# DDC118_eval2_rev1D.net
KiCad netlist of a schematic drawn in EAGLE
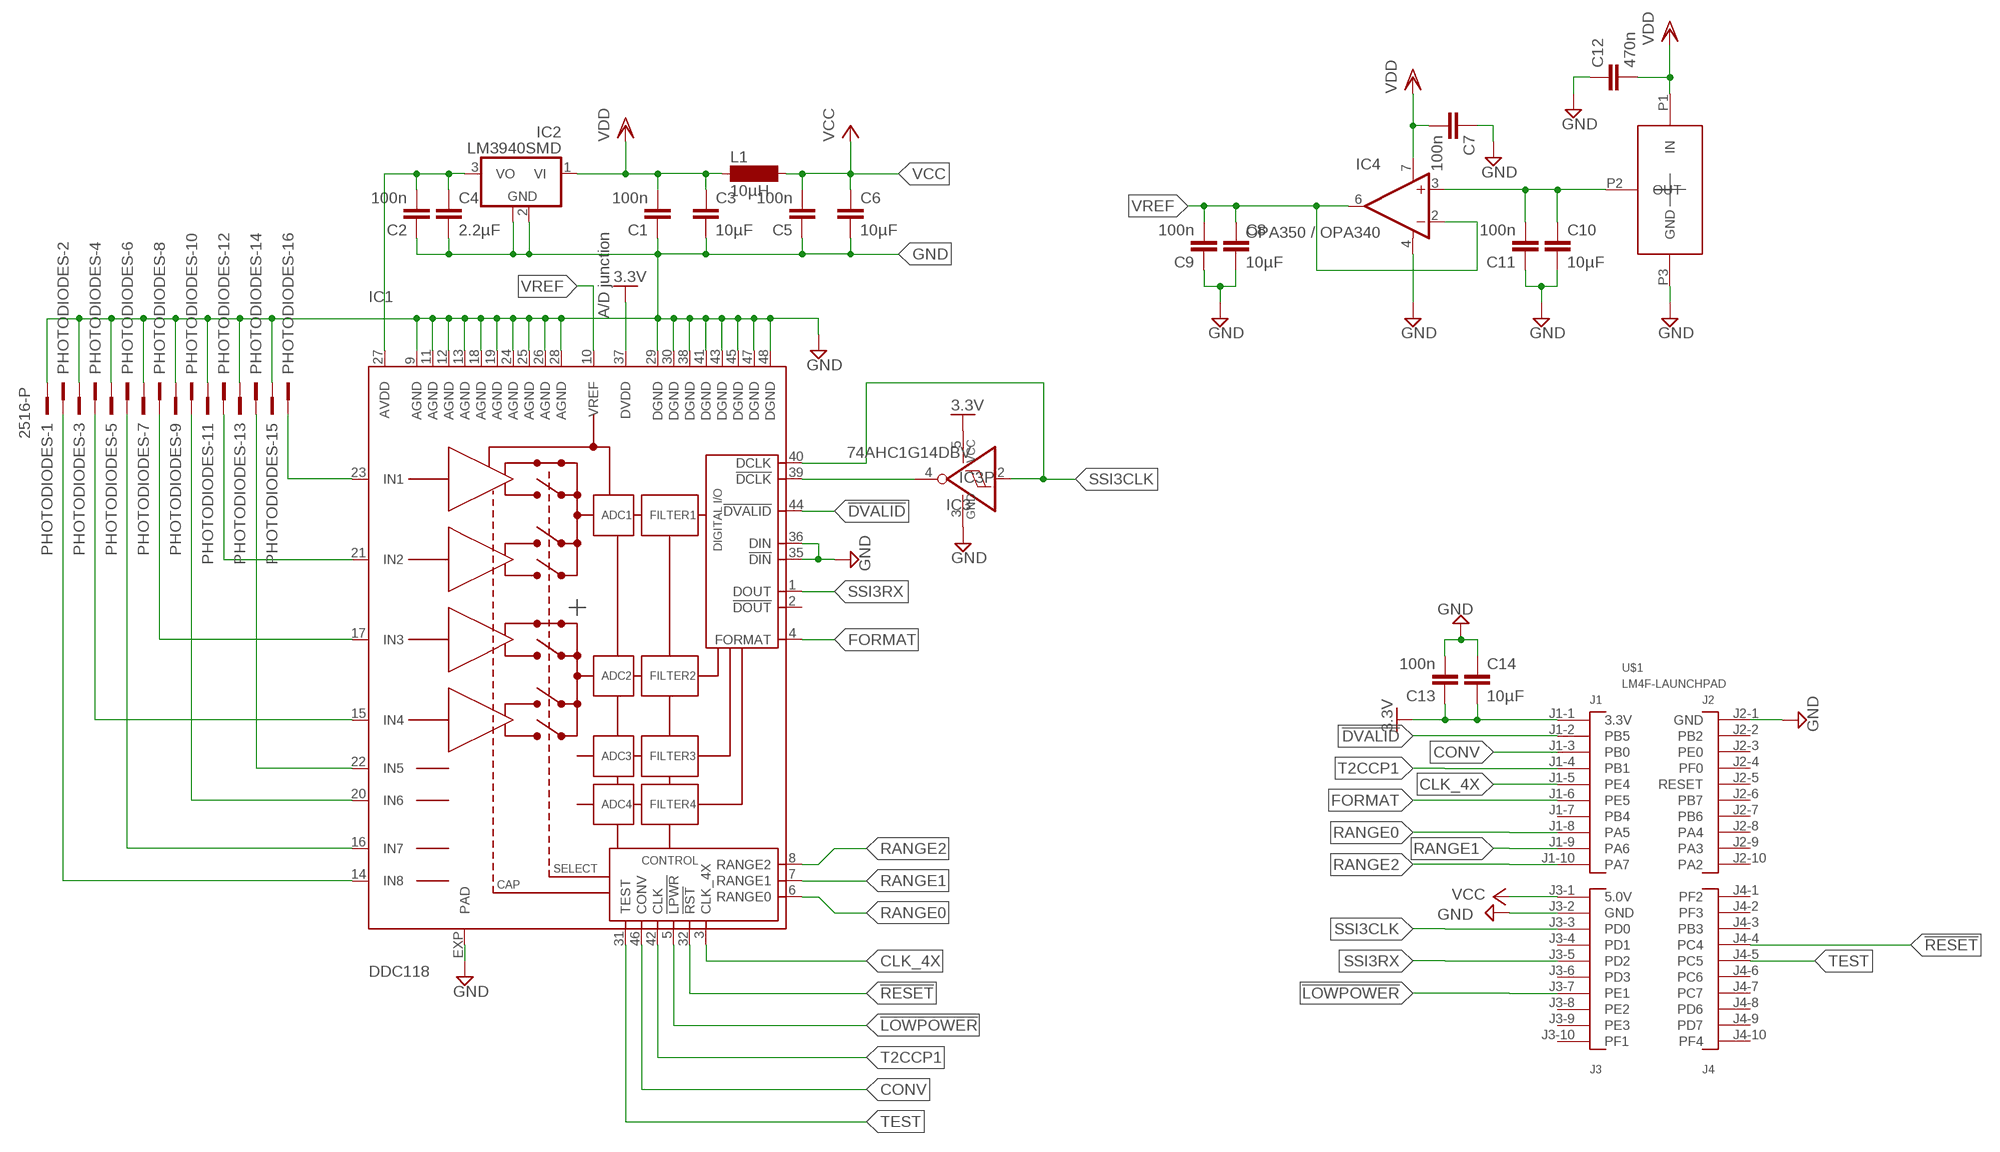
[diagram p0: schematic, sheet 1]

(export (version "E")
  (design (tool "Eeschema 10.0.6"))
  (components
    (comp (ref "C1")
      (value "100n")
      (footprint "eagle-import:C0805K")
      (libsource (lib "eagle-import") (part "C-EUC0805K"))
    )
    (comp (ref "C2")
      (value "100n")
      (footprint "eagle-import:C0805K")
      (libsource (lib "eagle-import") (part "C-EUC0805K"))
    )
    (comp (ref "C3")
      (value "10µF")
      (footprint "eagle-import:C0805")
      (libsource (lib "eagle-import") (part "C-EUC0805"))
    )
    (comp (ref "C4")
      (value "2.2µF")
      (footprint "eagle-import:C0805")
      (libsource (lib "eagle-import") (part "C-EUC0805"))
    )
    (comp (ref "C5")
      (value "100n")
      (footprint "eagle-import:C0805K")
      (libsource (lib "eagle-import") (part "C-EUC0805K"))
    )
    (comp (ref "C6")
      (value "10µF")
      (footprint "eagle-import:C0805")
      (libsource (lib "eagle-import") (part "C-EUC0805"))
    )
    (comp (ref "C7")
      (value "100n")
      (footprint "eagle-import:C0805K")
      (libsource (lib "eagle-import") (part "C-EUC0805K"))
    )
    (comp (ref "C8")
      (value "10µF")
      (footprint "eagle-import:C0805")
      (libsource (lib "eagle-import") (part "C-EUC0805"))
    )
    (comp (ref "C9")
      (value "100n")
      (footprint "eagle-import:C0805K")
      (libsource (lib "eagle-import") (part "C-EUC0805K"))
    )
    (comp (ref "C10")
      (value "10µF")
      (footprint "eagle-import:C0805")
      (libsource (lib "eagle-import") (part "C-EUC0805"))
    )
    (comp (ref "C11")
      (value "100n")
      (footprint "eagle-import:C0805K")
      (libsource (lib "eagle-import") (part "C-EUC0805K"))
    )
    (comp (ref "C12")
      (value "470n")
      (footprint "eagle-import:C0805K")
      (libsource (lib "eagle-import") (part "C-EUC0805K"))
    )
    (comp (ref "C13")
      (value "100n")
      (footprint "eagle-import:C0805K")
      (libsource (lib "eagle-import") (part "C-EUC0805K"))
    )
    (comp (ref "C14")
      (value "10µF")
      (footprint "eagle-import:C0805")
      (libsource (lib "eagle-import") (part "C-EUC0805"))
    )
    (comp (ref "IC1")
      (value "DDC118")
      (footprint "eagle-import:RGZ_S-PVQFN-N48")
      (libsource (lib "eagle-import") (part "DDC118"))
    )
    (comp (ref "IC2")
      (value "LM3940SMD")
      (footprint "eagle-import:SOT223")
      (libsource (lib "eagle-import") (part "LM3940SMD"))
    )
    (comp (ref "IC3")
      (value "74AHC1G14DBV")
      (footprint "eagle-import:SOT23-5")
      (libsource (lib "eagle-import") (part "741G14DBVAHC"))
    )
    (comp (ref "IC4")
      (value "OPA350 / OPA340")
      (footprint "eagle-import:SO08")
      (fields (field (name "MPN") "OPA340UA"))
      (libsource (lib "eagle-import") (part "OPA340U"))
    )
    (comp (ref "L1")
      (value "10µH")
      (footprint "eagle-import:MS50")
      (libsource (lib "eagle-import") (part "MS50"))
    )
    (comp (ref "PHOTODIODES")
      (value "2516-P")
      (footprint "eagle-import:PAK100_2500-16-PADS")
      (libsource (lib "eagle-import") (part "2516-P"))
    )
    (comp (ref "U$1")
      (value "LM4F-LAUNCHPAD")
      (footprint "eagle-import:LM4F120-LAUNCHPAD")
      (libsource (lib "eagle-import") (part "LM4F-LAUNCHPAD"))
    )
    (comp (ref "U1")
      (value "REF30XX")
      (footprint "eagle-import:SOT-23")
      (libsource (lib "eagle-import") (part "REF30XX"))
    )
  )
  (nets
    (net (code "1") (name "/PF2") (class "Default")
      (node (ref "U$1") (pin "J4-1") (pinfunction "PF2_J4-1") (pintype "power_in"))
    )
    (net (code "2") (name "/~{DVALID}") (class "Default")
      (node (ref "IC1") (pin "44") (pinfunction "~{DVALID}_44") (pintype "output"))
      (node (ref "U$1") (pin "J1-2") (pinfunction "PB5_J1-2") (pintype "bidirectional"))
    )
    (net (code "3") (name "/~{LOWPOWER}") (class "Default")
      (node (ref "IC1") (pin "5") (pinfunction "~{LPWR}_5") (pintype "input"))
      (node (ref "U$1") (pin "J3-7") (pinfunction "PE1_J3-7") (pintype "bidirectional"))
    )
    (net (code "4") (name "/~{RESET}") (class "Default")
      (node (ref "IC1") (pin "32") (pinfunction "~{RST}_32") (pintype "input"))
      (node (ref "U$1") (pin "J4-4") (pinfunction "PC4_J4-4") (pintype "bidirectional"))
    )
    (net (code "5") (name "3.3V") (class "Default")
      (node (ref "C13") (pin "1") (pinfunction "1_1") (pintype "passive"))
      (node (ref "C14") (pin "2") (pinfunction "2_2") (pintype "passive"))
      (node (ref "IC1") (pin "37") (pinfunction "DVDD_37") (pintype "power_in"))
      (node (ref "IC3") (pin "5") (pinfunction "VCC_5") (pintype "power_in"))
      (node (ref "U$1") (pin "J1-1") (pinfunction "3.3V_J1-1") (pintype "power_in"))
    )
    (net (code "6") (name "CLK_4X") (class "Default")
      (node (ref "IC1") (pin "3") (pinfunction "CLK_4X_3") (pintype "input"))
      (node (ref "U$1") (pin "J1-5") (pinfunction "PE4_J1-5") (pintype "bidirectional"))
    )
    (net (code "7") (name "CONV") (class "Default")
      (node (ref "IC1") (pin "46") (pinfunction "CONV_46") (pintype "input"))
      (node (ref "U$1") (pin "J1-3") (pinfunction "PB0_J1-3") (pintype "bidirectional"))
    )
    (net (code "8") (name "FORMAT") (class "Default")
      (node (ref "IC1") (pin "4") (pinfunction "FORMAT_4") (pintype "output"))
      (node (ref "U$1") (pin "J1-6") (pinfunction "PE5_J1-6") (pintype "bidirectional"))
    )
    (net (code "9") (name "GND") (class "Default")
      (node (ref "C1") (pin "1") (pinfunction "1_1") (pintype "passive"))
      (node (ref "C10") (pin "2") (pinfunction "2_2") (pintype "passive"))
      (node (ref "C11") (pin "1") (pinfunction "1_1") (pintype "passive"))
      (node (ref "C12") (pin "1") (pinfunction "1_1") (pintype "passive"))
      (node (ref "C13") (pin "2") (pinfunction "2_2") (pintype "passive"))
      (node (ref "C14") (pin "1") (pinfunction "1_1") (pintype "passive"))
      (node (ref "C2") (pin "1") (pinfunction "1_1") (pintype "passive"))
      (node (ref "C3") (pin "2") (pinfunction "2_2") (pintype "passive"))
      (node (ref "C4") (pin "2") (pinfunction "2_2") (pintype "passive"))
      (node (ref "C5") (pin "1") (pinfunction "1_1") (pintype "passive"))
      (node (ref "C6") (pin "2") (pinfunction "2_2") (pintype "passive"))
      (node (ref "C7") (pin "1") (pinfunction "1_1") (pintype "passive"))
      (node (ref "C8") (pin "2") (pinfunction "2_2") (pintype "passive"))
      (node (ref "C9") (pin "1") (pinfunction "1_1") (pintype "passive"))
      (node (ref "IC1") (pin "11") (pinfunction "AGND_11") (pintype "power_in"))
      (node (ref "IC1") (pin "12") (pinfunction "AGND_12") (pintype "power_in"))
      (node (ref "IC1") (pin "13") (pinfunction "AGND_13") (pintype "power_in"))
      (node (ref "IC1") (pin "18") (pinfunction "AGND_18") (pintype "power_in"))
      (node (ref "IC1") (pin "19") (pinfunction "AGND_19") (pintype "power_in"))
      (node (ref "IC1") (pin "24") (pinfunction "AGND_24") (pintype "power_in"))
      (node (ref "IC1") (pin "25") (pinfunction "AGND_25") (pintype "power_in"))
      (node (ref "IC1") (pin "26") (pinfunction "AGND_26") (pintype "power_in"))
      (node (ref "IC1") (pin "28") (pinfunction "AGND_28") (pintype "power_in"))
      (node (ref "IC1") (pin "29") (pinfunction "DGND_29") (pintype "power_in"))
      (node (ref "IC1") (pin "30") (pinfunction "DGND_30") (pintype "power_in"))
      (node (ref "IC1") (pin "35") (pinfunction "~{DIN}_35") (pintype "input"))
      (node (ref "IC1") (pin "36") (pinfunction "DIN_36") (pintype "input"))
      (node (ref "IC1") (pin "38") (pinfunction "DGND_38") (pintype "power_in"))
      (node (ref "IC1") (pin "41") (pinfunction "DGND_41") (pintype "power_in"))
      (node (ref "IC1") (pin "43") (pinfunction "DGND_43") (pintype "power_in"))
      (node (ref "IC1") (pin "45") (pinfunction "DGND_45") (pintype "power_in"))
      (node (ref "IC1") (pin "47") (pinfunction "DGND_47") (pintype "power_in"))
      (node (ref "IC1") (pin "48") (pinfunction "DGND_48") (pintype "power_in"))
      (node (ref "IC1") (pin "9") (pinfunction "AGND_9") (pintype "power_in"))
      (node (ref "IC1") (pin "EXP") (pinfunction "PAD_EXP") (pintype "power_in"))
      (node (ref "IC2") (pin "2") (pinfunction "GND_2") (pintype "passive"))
      (node (ref "IC2") (pin "4") (pinfunction "GND_4") (pintype "passive"))
      (node (ref "IC3") (pin "3") (pinfunction "GND_3") (pintype "power_in"))
      (node (ref "IC4") (pin "4") (pinfunction "V-_4") (pintype "power_in"))
      (node (ref "PHOTODIODES") (pin "1") (pinfunction "KL_1") (pintype "passive"))
      (node (ref "PHOTODIODES") (pin "11") (pinfunction "KL_11") (pintype "passive"))
      (node (ref "PHOTODIODES") (pin "13") (pinfunction "KL_13") (pintype "passive"))
      (node (ref "PHOTODIODES") (pin "15") (pinfunction "KL_15") (pintype "passive"))
      (node (ref "PHOTODIODES") (pin "3") (pinfunction "KL_3") (pintype "passive"))
      (node (ref "PHOTODIODES") (pin "5") (pinfunction "KL_5") (pintype "passive"))
      (node (ref "PHOTODIODES") (pin "7") (pinfunction "KL_7") (pintype "passive"))
      (node (ref "PHOTODIODES") (pin "9") (pinfunction "KL_9") (pintype "passive"))
      (node (ref "U$1") (pin "J2-1") (pinfunction "GND_J2-1") (pintype "power_in"))
      (node (ref "U$1") (pin "J3-2") (pinfunction "GND_J3-2") (pintype "bidirectional"))
      (node (ref "U1") (pin "P3") (pinfunction "GND_P3") (pintype "bidirectional"))
    )
    (net (code "10") (name "Net-(IC1-AVDD)") (class "Default")
      (node (ref "C2") (pin "2") (pinfunction "2_2") (pintype "passive"))
      (node (ref "C4") (pin "1") (pinfunction "1_1") (pintype "passive"))
      (node (ref "IC1") (pin "27") (pinfunction "AVDD_27") (pintype "power_in"))
      (node (ref "IC2") (pin "3") (pinfunction "VO_3") (pintype "passive"))
    )
    (net (code "11") (name "Net-(IC1-IN1)") (class "Default")
      (node (ref "IC1") (pin "23") (pinfunction "IN1_23") (pintype "input"))
      (node (ref "PHOTODIODES") (pin "16") (pinfunction "KL_16") (pintype "passive"))
    )
    (net (code "12") (name "Net-(IC1-IN2)") (class "Default")
      (node (ref "IC1") (pin "21") (pinfunction "IN2_21") (pintype "input"))
      (node (ref "PHOTODIODES") (pin "12") (pinfunction "KL_12") (pintype "passive"))
    )
    (net (code "13") (name "Net-(IC1-IN3)") (class "Default")
      (node (ref "IC1") (pin "17") (pinfunction "IN3_17") (pintype "input"))
      (node (ref "PHOTODIODES") (pin "8") (pinfunction "KL_8") (pintype "passive"))
    )
    (net (code "14") (name "Net-(IC1-IN4)") (class "Default")
      (node (ref "IC1") (pin "15") (pinfunction "IN4_15") (pintype "input"))
      (node (ref "PHOTODIODES") (pin "4") (pinfunction "KL_4") (pintype "passive"))
    )
    (net (code "15") (name "Net-(IC1-IN5)") (class "Default")
      (node (ref "IC1") (pin "22") (pinfunction "IN5_22") (pintype "input"))
      (node (ref "PHOTODIODES") (pin "14") (pinfunction "KL_14") (pintype "passive"))
    )
    (net (code "16") (name "Net-(IC1-IN6)") (class "Default")
      (node (ref "IC1") (pin "20") (pinfunction "IN6_20") (pintype "input"))
      (node (ref "PHOTODIODES") (pin "10") (pinfunction "KL_10") (pintype "passive"))
    )
    (net (code "17") (name "Net-(IC1-IN7)") (class "Default")
      (node (ref "IC1") (pin "16") (pinfunction "IN7_16") (pintype "input"))
      (node (ref "PHOTODIODES") (pin "6") (pinfunction "KL_6") (pintype "passive"))
    )
    (net (code "18") (name "Net-(IC1-IN8)") (class "Default")
      (node (ref "IC1") (pin "14") (pinfunction "IN8_14") (pintype "input"))
      (node (ref "PHOTODIODES") (pin "2") (pinfunction "KL_2") (pintype "passive"))
    )
    (net (code "19") (name "Net-(IC1-~{DCLK})") (class "Default")
      (node (ref "IC1") (pin "39") (pinfunction "~{DCLK}_39") (pintype "input"))
      (node (ref "IC3") (pin "4") (pinfunction "O_4") (pintype "output"))
    )
    (net (code "20") (name "Net-(IC4-+IN)") (class "Default")
      (node (ref "C10") (pin "1") (pinfunction "1_1") (pintype "passive"))
      (node (ref "C11") (pin "2") (pinfunction "2_2") (pintype "passive"))
      (node (ref "IC4") (pin "3") (pinfunction "+IN_3") (pintype "input"))
      (node (ref "U1") (pin "P2") (pinfunction "OUT_P2") (pintype "bidirectional"))
    )
    (net (code "21") (name "RANGE0") (class "Default")
      (node (ref "IC1") (pin "6") (pinfunction "RANGE0_6") (pintype "output"))
      (node (ref "U$1") (pin "J1-8") (pinfunction "PA5_J1-8") (pintype "bidirectional"))
    )
    (net (code "22") (name "RANGE1") (class "Default")
      (node (ref "IC1") (pin "7") (pinfunction "RANGE1_7") (pintype "output"))
      (node (ref "U$1") (pin "J1-9") (pinfunction "PA6_J1-9") (pintype "bidirectional"))
    )
    (net (code "23") (name "RANGE2") (class "Default")
      (node (ref "IC1") (pin "8") (pinfunction "RANGE2_8") (pintype "output"))
      (node (ref "U$1") (pin "J1-10") (pinfunction "PA7_J1-10") (pintype "bidirectional"))
    )
    (net (code "24") (name "SSI3CLK") (class "Default")
      (node (ref "IC1") (pin "40") (pinfunction "DCLK_40") (pintype "input"))
      (node (ref "IC3") (pin "2") (pinfunction "I_2") (pintype "input"))
      (node (ref "U$1") (pin "J3-3") (pinfunction "PD0_J3-3") (pintype "bidirectional"))
    )
    (net (code "25") (name "SSI3RX") (class "Default")
      (node (ref "IC1") (pin "1") (pinfunction "DOUT_1") (pintype "output"))
      (node (ref "U$1") (pin "J3-5") (pinfunction "PD2_J3-5") (pintype "bidirectional"))
    )
    (net (code "26") (name "T2CCP1") (class "Default")
      (node (ref "IC1") (pin "42") (pinfunction "CLK_42") (pintype "input"))
      (node (ref "U$1") (pin "J1-4") (pinfunction "PB1_J1-4") (pintype "bidirectional"))
    )
    (net (code "27") (name "TEST") (class "Default")
      (node (ref "IC1") (pin "31") (pinfunction "TEST_31") (pintype "power_in"))
      (node (ref "U$1") (pin "J4-5") (pinfunction "PC5_J4-5") (pintype "bidirectional"))
    )
    (net (code "28") (name "VCC") (class "Default")
      (node (ref "C5") (pin "2") (pinfunction "2_2") (pintype "passive"))
      (node (ref "C6") (pin "1") (pinfunction "1_1") (pintype "passive"))
      (node (ref "L1") (pin "2") (pinfunction "2_2") (pintype "passive"))
      (node (ref "U$1") (pin "J3-1") (pinfunction "5.0V_J3-1") (pintype "power_in"))
    )
    (net (code "29") (name "VDD") (class "Default")
      (node (ref "C1") (pin "2") (pinfunction "2_2") (pintype "passive"))
      (node (ref "C12") (pin "2") (pinfunction "2_2") (pintype "passive"))
      (node (ref "C3") (pin "1") (pinfunction "1_1") (pintype "passive"))
      (node (ref "C7") (pin "2") (pinfunction "2_2") (pintype "passive"))
      (node (ref "IC2") (pin "1") (pinfunction "VI_1") (pintype "input"))
      (node (ref "IC4") (pin "7") (pinfunction "V+_7") (pintype "power_in"))
      (node (ref "L1") (pin "1") (pinfunction "1_1") (pintype "passive"))
      (node (ref "U1") (pin "P1") (pinfunction "IN_P1") (pintype "bidirectional"))
    )
    (net (code "30") (name "VREF") (class "Default")
      (node (ref "C8") (pin "1") (pinfunction "1_1") (pintype "passive"))
      (node (ref "C9") (pin "2") (pinfunction "2_2") (pintype "passive"))
      (node (ref "IC1") (pin "10") (pinfunction "VREF_10") (pintype "passive"))
      (node (ref "IC4") (pin "2") (pinfunction "-IN_2") (pintype "input"))
      (node (ref "IC4") (pin "6") (pinfunction "OUT_6") (pintype "output"))
    )
    (net (code "31") (name "unconnected-(IC1-~{DOUT}-Pad2)") (class "Default")
      (node (ref "IC1") (pin "2") (pinfunction "~{DOUT}_2") (pintype "output"))
    )
    (net (code "32") (name "unconnected-(U$1-PA2-PadJ2-10)") (class "Default")
      (node (ref "U$1") (pin "J2-10") (pinfunction "PA2_J2-10") (pintype "bidirectional"))
    )
    (net (code "33") (name "unconnected-(U$1-PA3-PadJ2-9)") (class "Default")
      (node (ref "U$1") (pin "J2-9") (pinfunction "PA3_J2-9") (pintype "bidirectional"))
    )
    (net (code "34") (name "unconnected-(U$1-PA4-PadJ2-8)") (class "Default")
      (node (ref "U$1") (pin "J2-8") (pinfunction "PA4_J2-8") (pintype "bidirectional"))
    )
    (net (code "35") (name "unconnected-(U$1-PB2-PadJ2-2)") (class "Default")
      (node (ref "U$1") (pin "J2-2") (pinfunction "PB2_J2-2") (pintype "bidirectional"))
    )
    (net (code "36") (name "unconnected-(U$1-PB3-PadJ4-3)") (class "Default")
      (node (ref "U$1") (pin "J4-3") (pinfunction "PB3_J4-3") (pintype "bidirectional"))
    )
    (net (code "37") (name "unconnected-(U$1-PB4-PadJ1-7)") (class "Default")
      (node (ref "U$1") (pin "J1-7") (pinfunction "PB4_J1-7") (pintype "bidirectional"))
    )
    (net (code "38") (name "unconnected-(U$1-PB6-PadJ2-7)") (class "Default")
      (node (ref "U$1") (pin "J2-7") (pinfunction "PB6_J2-7") (pintype "bidirectional"))
    )
    (net (code "39") (name "unconnected-(U$1-PB7-PadJ2-6)") (class "Default")
      (node (ref "U$1") (pin "J2-6") (pinfunction "PB7_J2-6") (pintype "bidirectional"))
    )
    (net (code "40") (name "unconnected-(U$1-PC6-PadJ4-6)") (class "Default")
      (node (ref "U$1") (pin "J4-6") (pinfunction "PC6_J4-6") (pintype "bidirectional"))
    )
    (net (code "41") (name "unconnected-(U$1-PC7-PadJ4-7)") (class "Default")
      (node (ref "U$1") (pin "J4-7") (pinfunction "PC7_J4-7") (pintype "bidirectional"))
    )
    (net (code "42") (name "unconnected-(U$1-PD1-PadJ3-4)") (class "Default")
      (node (ref "U$1") (pin "J3-4") (pinfunction "PD1_J3-4") (pintype "bidirectional"))
    )
    (net (code "43") (name "unconnected-(U$1-PD3-PadJ3-6)") (class "Default")
      (node (ref "U$1") (pin "J3-6") (pinfunction "PD3_J3-6") (pintype "bidirectional"))
    )
    (net (code "44") (name "unconnected-(U$1-PD6-PadJ4-8)") (class "Default")
      (node (ref "U$1") (pin "J4-8") (pinfunction "PD6_J4-8") (pintype "bidirectional"))
    )
    (net (code "45") (name "unconnected-(U$1-PD7-PadJ4-9)") (class "Default")
      (node (ref "U$1") (pin "J4-9") (pinfunction "PD7_J4-9") (pintype "bidirectional"))
    )
    (net (code "46") (name "unconnected-(U$1-PE0-PadJ2-3)") (class "Default")
      (node (ref "U$1") (pin "J2-3") (pinfunction "PE0_J2-3") (pintype "bidirectional"))
    )
    (net (code "47") (name "unconnected-(U$1-PE2-PadJ3-8)") (class "Default")
      (node (ref "U$1") (pin "J3-8") (pinfunction "PE2_J3-8") (pintype "bidirectional"))
    )
    (net (code "48") (name "unconnected-(U$1-PE3-PadJ3-9)") (class "Default")
      (node (ref "U$1") (pin "J3-9") (pinfunction "PE3_J3-9") (pintype "bidirectional"))
    )
    (net (code "49") (name "unconnected-(U$1-PF0-PadJ2-4)") (class "Default")
      (node (ref "U$1") (pin "J2-4") (pinfunction "PF0_J2-4") (pintype "bidirectional"))
    )
    (net (code "50") (name "unconnected-(U$1-PF1-PadJ3-10)") (class "Default")
      (node (ref "U$1") (pin "J3-10") (pinfunction "PF1_J3-10") (pintype "bidirectional"))
    )
    (net (code "51") (name "unconnected-(U$1-PF3-PadJ4-2)") (class "Default")
      (node (ref "U$1") (pin "J4-2") (pinfunction "PF3_J4-2") (pintype "bidirectional"))
    )
    (net (code "52") (name "unconnected-(U$1-PF4-PadJ4-10)") (class "Default")
      (node (ref "U$1") (pin "J4-10") (pinfunction "PF4_J4-10") (pintype "bidirectional"))
    )
    (net (code "53") (name "unconnected-(U$1-RESET-PadJ2-5)") (class "Default")
      (node (ref "U$1") (pin "J2-5") (pinfunction "RESET_J2-5") (pintype "bidirectional"))
    )
  )
)
